# LM_386_audio_amplifier.net
KiCad netlist of a schematic drawn in EAGLE
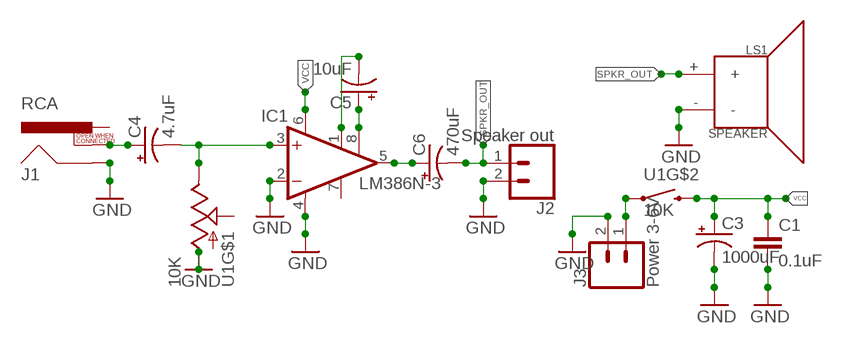
[diagram p0: schematic, sheet 1]

(export (version "E")
  (design (tool "Eeschema 10.0.6"))
  (components
    (comp (ref "C1")
      (value "0.1uF")
      (footprint "eagle-import:0603")
      (libsource (lib "eagle-import") (part "0.1UF-0603-25V-5%"))
    )
    (comp (ref "C3")
      (value "1000uF")
      (footprint "eagle-import:NIC_10X10.5_CAP")
      (libsource (lib "eagle-import") (part "100UF-POLAR-10X10.5-63V-20%"))
    )
    (comp (ref "C4")
      (value "4.7uF")
      (footprint "eagle-import:NIC_10X10.5_CAP")
      (libsource (lib "eagle-import") (part "100UF-POLAR-10X10.5-63V-20%"))
    )
    (comp (ref "C5")
      (value "10uF")
      (footprint "eagle-import:NIC_10X10.5_CAP")
      (libsource (lib "eagle-import") (part "100UF-POLAR-10X10.5-63V-20%"))
    )
    (comp (ref "C6")
      (value "470uF")
      (footprint "eagle-import:NIC_10X10.5_CAP")
      (libsource (lib "eagle-import") (part "100UF-POLAR-10X10.5-63V-20%"))
    )
    (comp (ref "IC1")
      (value "LM386N-3")
      (footprint "eagle-import:DIL08")
      (libsource (lib "eagle-import") (part "LM386?-N3"))
    )
    (comp (ref "J1")
      (value "RCA")
      (footprint "eagle-import:RCA")
      (libsource (lib "eagle-import") (part "RCA"))
    )
    (comp (ref "J2")
      (value "Speaker out")
      (footprint "eagle-import:JST-2-PTH-NS")
      (libsource (lib "eagle-import") (part "CONN_02-JST-2-PTH-NO_SILK"))
    )
    (comp (ref "J3")
      (value "Power 3-6V")
      (footprint "eagle-import:JST-2-PTH-NS")
      (libsource (lib "eagle-import") (part "CONN_02-JST-2-PTH-NO_SILK"))
    )
    (comp (ref "LS1")
      (value "SPEAKER")
      (footprint "eagle-import:PCB_MOUNT_SPEAKER")
      (libsource (lib "eagle-import") (part "SPEAKER"))
    )
    (comp (ref "U1")
      (value "10K")
      (footprint "eagle-import:POT_PTH")
      (libsource (lib "eagle-import") (part "POT_SWITCHPOT_PTH"))
    )
  )
  (nets
    (net (code "1") (name "GND") (class "Default")
      (node (ref "C1") (pin "2") (pinfunction "2_2") (pintype "passive"))
      (node (ref "C3") (pin "-") (pinfunction "-_-") (pintype "passive"))
      (node (ref "IC1") (pin "2") (pinfunction "-IN_2") (pintype "input"))
      (node (ref "IC1") (pin "4") (pinfunction "GND_4") (pintype "power_in"))
      (node (ref "J1") (pin "SHELL") (pinfunction "SHELL_SHELL") (pintype "bidirectional"))
      (node (ref "J2") (pin "2") (pinfunction "2_2") (pintype "passive"))
      (node (ref "J3") (pin "2") (pinfunction "2_2") (pintype "passive"))
      (node (ref "LS1") (pin "-") (pinfunction "-_-") (pintype "bidirectional"))
      (node (ref "U1") (pin "E@1") (pinfunction "A_E@1") (pintype "passive"))
    )
    (net (code "2") (name "Net-(C4-Pad+)") (class "Default")
      (node (ref "C4") (pin "+") (pinfunction "+_+") (pintype "passive"))
      (node (ref "J1") (pin "SWITCH") (pinfunction "SWITCH_SWITCH") (pintype "bidirectional"))
    )
    (net (code "3") (name "Net-(C5-Pad+)") (class "Default")
      (node (ref "C5") (pin "+") (pinfunction "+_+") (pintype "passive"))
      (node (ref "IC1") (pin "8") (pinfunction "GAIN_8") (pintype "passive"))
    )
    (net (code "4") (name "Net-(C5-Pad-)") (class "Default")
      (node (ref "C5") (pin "-") (pinfunction "-_-") (pintype "passive"))
      (node (ref "IC1") (pin "1") (pinfunction "GAIN_1") (pintype "passive"))
    )
    (net (code "5") (name "Net-(IC1-+IN)") (class "Default")
      (node (ref "C4") (pin "-") (pinfunction "-_-") (pintype "passive"))
      (node (ref "IC1") (pin "3") (pinfunction "+IN_3") (pintype "input"))
      (node (ref "U1") (pin "E@2") (pinfunction "E_E@2") (pintype "passive"))
    )
    (net (code "6") (name "Net-(IC1-OUT)") (class "Default")
      (node (ref "C6") (pin "+") (pinfunction "+_+") (pintype "passive"))
      (node (ref "IC1") (pin "5") (pinfunction "OUT_5") (pintype "output"))
    )
    (net (code "7") (name "Net-(U1B-1)") (class "Default")
      (node (ref "J3") (pin "1") (pinfunction "1_1") (pintype "passive"))
      (node (ref "U1") (pin "S1") (pinfunction "1_S1") (pintype "passive"))
    )
    (net (code "8") (name "SPKR_OUT") (class "Default")
      (node (ref "C6") (pin "-") (pinfunction "-_-") (pintype "passive"))
      (node (ref "J2") (pin "1") (pinfunction "1_1") (pintype "passive"))
      (node (ref "LS1") (pin "+") (pinfunction "+_+") (pintype "bidirectional"))
    )
    (net (code "9") (name "VCC") (class "Default")
      (node (ref "C1") (pin "1") (pinfunction "1_1") (pintype "passive"))
      (node (ref "C3") (pin "+") (pinfunction "+_+") (pintype "passive"))
      (node (ref "IC1") (pin "6") (pinfunction "VS_6") (pintype "power_in"))
      (node (ref "U1") (pin "S2") (pinfunction "2_S2") (pintype "passive"))
    )
    (net (code "10") (name "unconnected-(IC1-BYPASS-Pad7)") (class "Default")
      (node (ref "IC1") (pin "7") (pinfunction "BYPASS_7") (pintype "passive"))
    )
    (net (code "11") (name "unconnected-(J1-PadPIN)") (class "Default")
      (node (ref "J1") (pin "PIN") (pinfunction "PIN_PIN") (pintype "bidirectional"))
    )
    (net (code "12") (name "unconnected-(U1A-S-PadWAND)") (class "Default")
      (node (ref "U1") (pin "WAND") (pinfunction "S_WAND") (pintype "passive"))
    )
  )
)
